# csi.net
KiCad netlist of a schematic drawn in Altium Designer
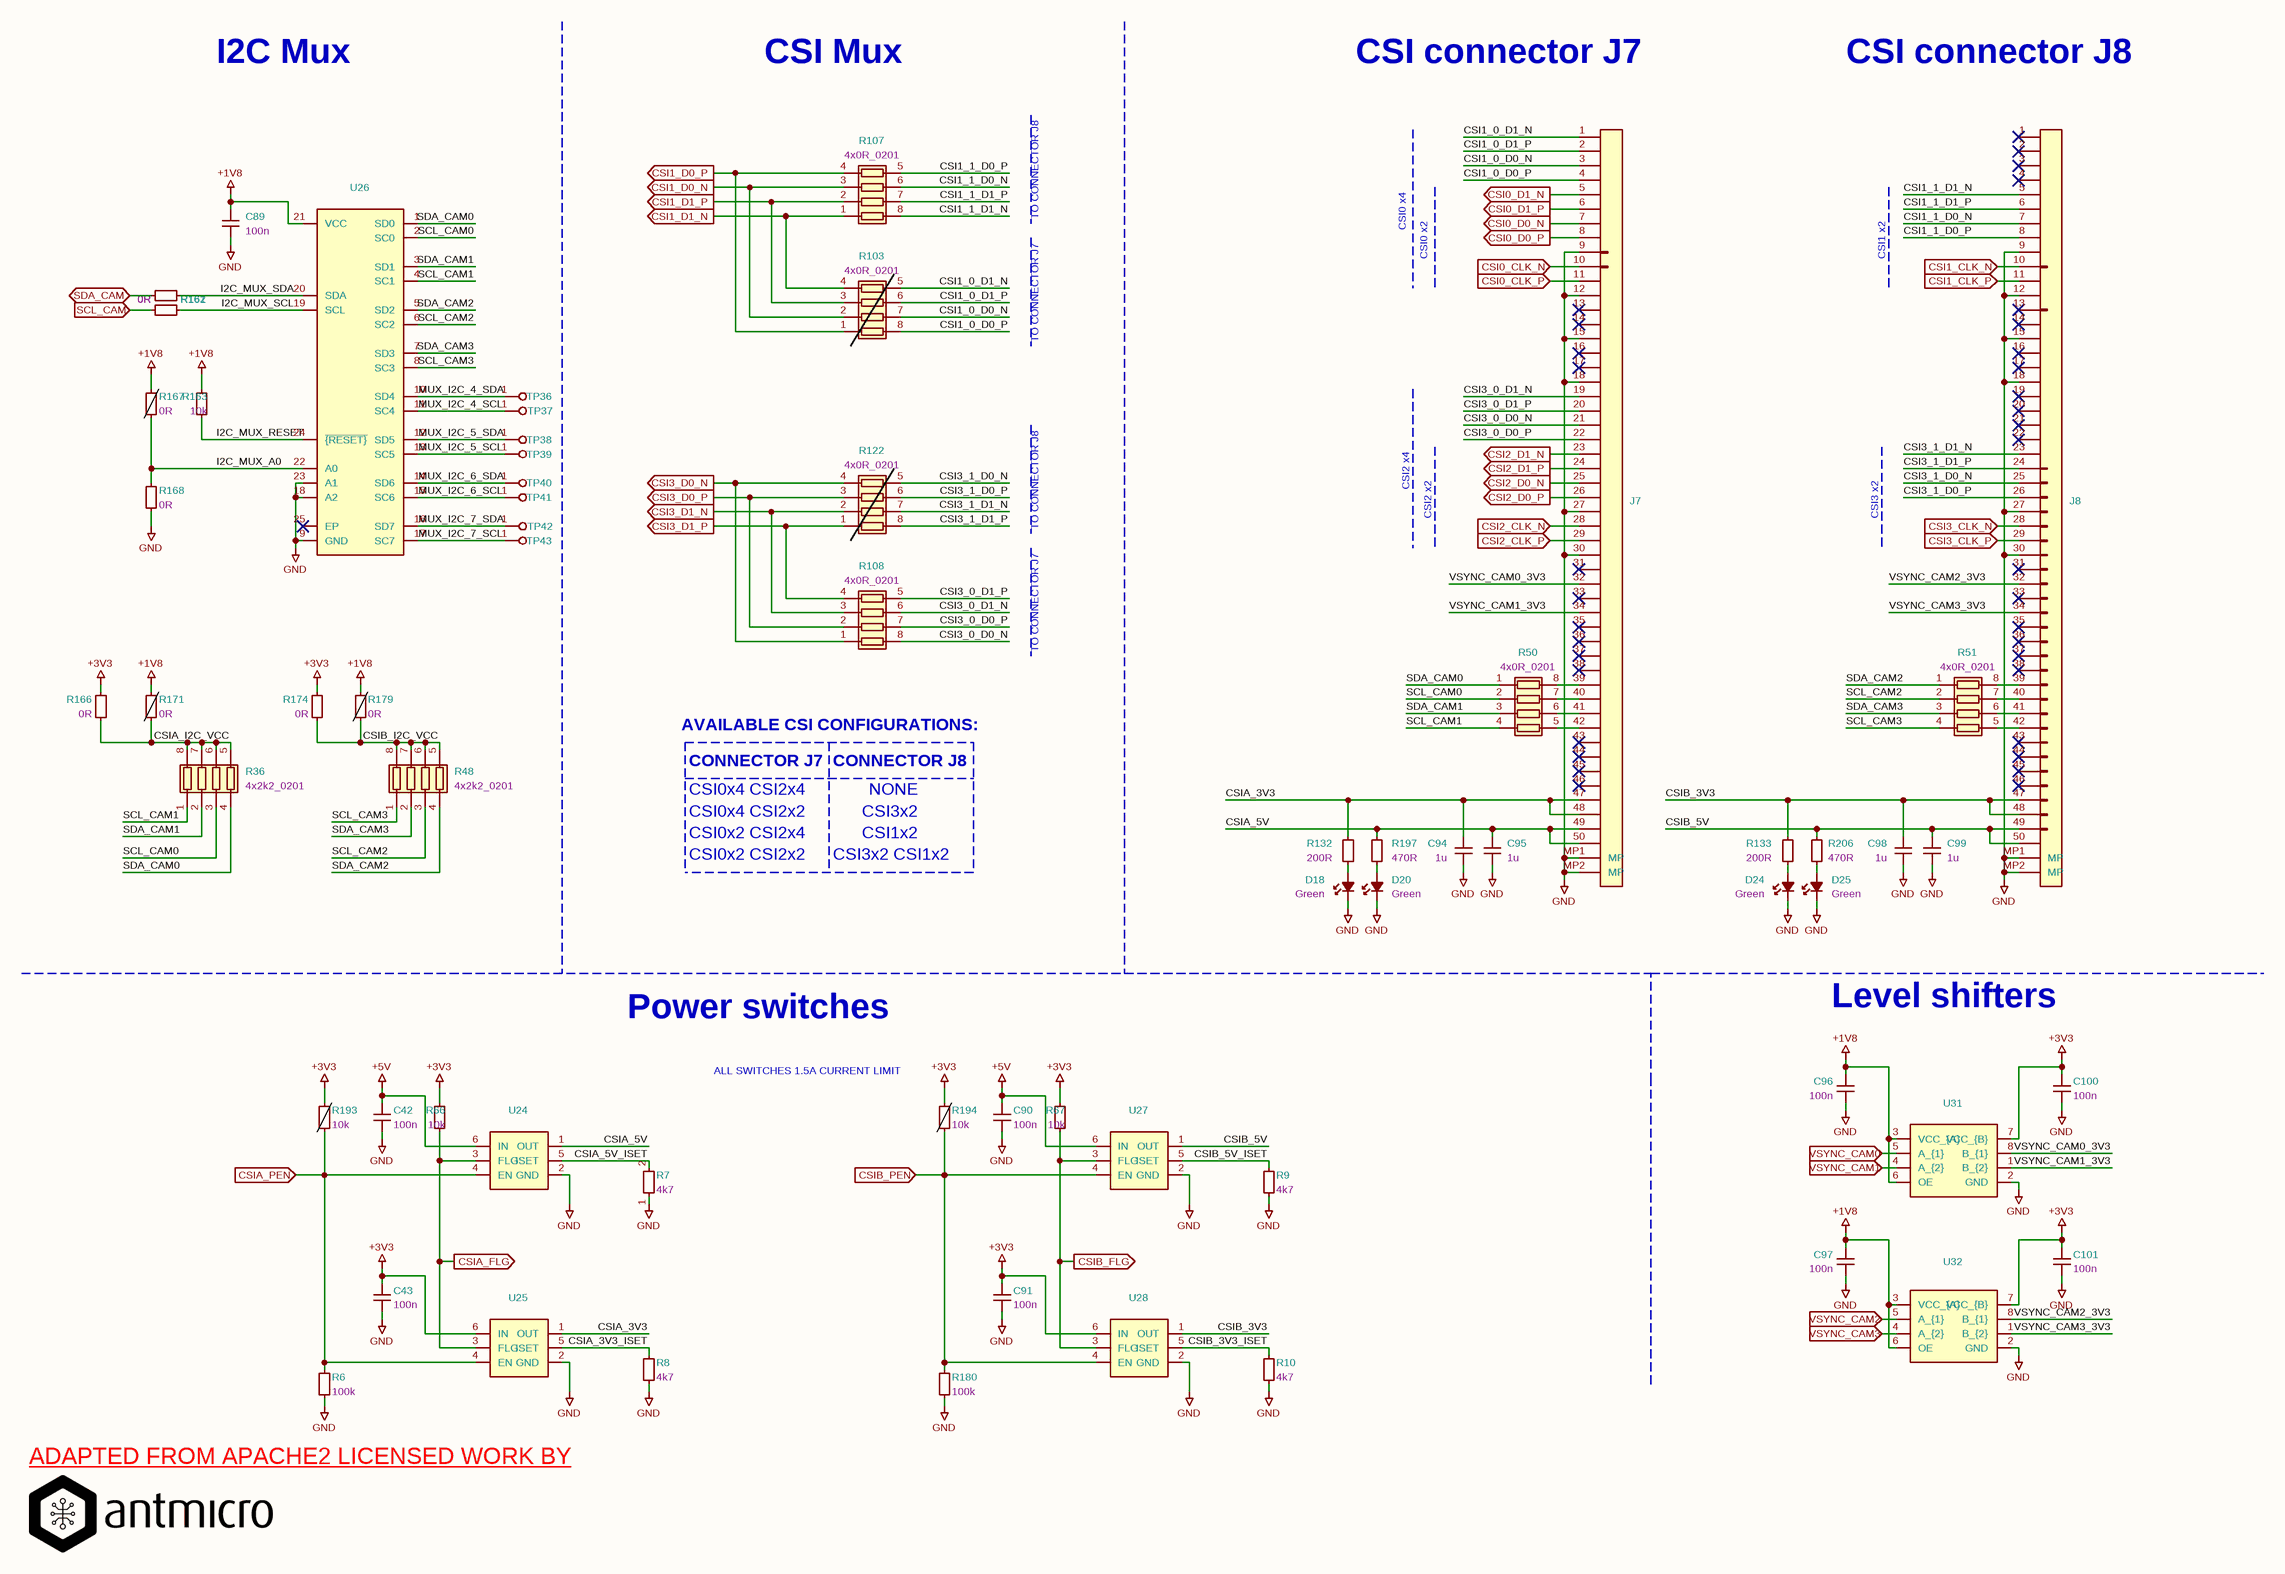
[diagram p0: csi.SchDoc]

(export (version "E")
  (design (tool "Eeschema 10.0.6"))
  (components
    (comp (ref "C42")
      (value "GRM155R61H104KE14D")
      (footprint "C_0402_1005Metric")
      (fields (field (name "VAL") "100n") (field (name "VOLTAGE") "50V") (field (name "AUTHOR") "Antmicro"))
      (libsource (lib "antmicroCapacitors0402") (part "C_100n_0402"))
    )
    (comp (ref "C43")
      (value "GRM155R61H104KE14D")
      (footprint "C_0402_1005Metric")
      (fields (field (name "VAL") "100n") (field (name "VOLTAGE") "50V") (field (name "AUTHOR") "Antmicro"))
      (libsource (lib "antmicroCapacitors0402") (part "C_100n_0402"))
    )
    (comp (ref "C89")
      (value "GRM155R61H104KE14D")
      (footprint "C_0402_1005Metric")
      (fields (field (name "VAL") "100n") (field (name "VOLTAGE") "50V") (field (name "AUTHOR") "Antmicro"))
      (libsource (lib "antmicroCapacitors0402") (part "C_100n_0402"))
    )
    (comp (ref "C90")
      (value "GRM155R61H104KE14D")
      (footprint "C_0402_1005Metric")
      (fields (field (name "VAL") "100n") (field (name "VOLTAGE") "50V") (field (name "AUTHOR") "Antmicro"))
      (libsource (lib "antmicroCapacitors0402") (part "C_100n_0402"))
    )
    (comp (ref "C91")
      (value "GRM155R61H104KE14D")
      (footprint "C_0402_1005Metric")
      (fields (field (name "VAL") "100n") (field (name "VOLTAGE") "50V") (field (name "AUTHOR") "Antmicro"))
      (libsource (lib "antmicroCapacitors0402") (part "C_100n_0402"))
    )
    (comp (ref "C94")
      (value "C1005X6S1A105K050BC")
      (footprint "C_0402_1005Metric")
      (fields (field (name "VAL") "1u") (field (name "AUTHOR") "Antmicro"))
      (libsource (lib "antmicroCapacitors0402") (part "C_1u_0402"))
    )
    (comp (ref "C95")
      (value "C1005X6S1A105K050BC")
      (footprint "C_0402_1005Metric")
      (fields (field (name "VAL") "1u") (field (name "AUTHOR") "Antmicro"))
      (libsource (lib "antmicroCapacitors0402") (part "C_1u_0402"))
    )
    (comp (ref "C96")
      (value "GRM155R61H104KE14D")
      (footprint "C_0402_1005Metric")
      (fields (field (name "VAL") "100n") (field (name "VOLTAGE") "50V") (field (name "AUTHOR") "Antmicro"))
      (libsource (lib "antmicroCapacitors0402") (part "C_100n_0402"))
    )
    (comp (ref "C97")
      (value "GRM155R61H104KE14D")
      (footprint "C_0402_1005Metric")
      (fields (field (name "VAL") "100n") (field (name "VOLTAGE") "50V") (field (name "AUTHOR") "Antmicro"))
      (libsource (lib "antmicroCapacitors0402") (part "C_100n_0402"))
    )
    (comp (ref "C98")
      (value "C1005X6S1A105K050BC")
      (footprint "C_0402_1005Metric")
      (fields (field (name "VAL") "1u") (field (name "AUTHOR") "Antmicro"))
      (libsource (lib "antmicroCapacitors0402") (part "C_1u_0402"))
    )
    (comp (ref "C99")
      (value "C1005X6S1A105K050BC")
      (footprint "C_0402_1005Metric")
      (fields (field (name "VAL") "1u") (field (name "AUTHOR") "Antmicro"))
      (libsource (lib "antmicroCapacitors0402") (part "C_1u_0402"))
    )
    (comp (ref "C100")
      (value "GRM155R61H104KE14D")
      (footprint "C_0402_1005Metric")
      (fields (field (name "VAL") "100n") (field (name "VOLTAGE") "50V") (field (name "AUTHOR") "Antmicro"))
      (libsource (lib "antmicroCapacitors0402") (part "C_100n_0402"))
    )
    (comp (ref "C101")
      (value "GRM155R61H104KE14D")
      (footprint "C_0402_1005Metric")
      (fields (field (name "VAL") "100n") (field (name "VOLTAGE") "50V") (field (name "AUTHOR") "Antmicro"))
      (libsource (lib "antmicroCapacitors0402") (part "C_100n_0402"))
    )
    (comp (ref "D18")
      (value "LTST-C190GKT")
      (footprint "LED_0603_1608Metric_G")
      (fields (field (name "COLOR") "Green") (field (name "AUTHOR") "Antmicro"))
      (libsource (lib "antmicroLEDIndicationDiscrete") (part "LED_G_0603_LTST-C190GKT"))
    )
    (comp (ref "D20")
      (value "LTST-C190GKT")
      (footprint "LED_0603_1608Metric_G")
      (fields (field (name "COLOR") "Green") (field (name "AUTHOR") "Antmicro"))
      (libsource (lib "antmicroLEDIndicationDiscrete") (part "LED_G_0603_LTST-C190GKT"))
    )
    (comp (ref "D24")
      (value "LTST-C190GKT")
      (footprint "LED_0603_1608Metric_G")
      (fields (field (name "COLOR") "Green") (field (name "AUTHOR") "Antmicro"))
      (libsource (lib "antmicroLEDIndicationDiscrete") (part "LED_G_0603_LTST-C190GKT"))
    )
    (comp (ref "D25")
      (value "LTST-C190GKT")
      (footprint "LED_0603_1608Metric_G")
      (fields (field (name "COLOR") "Green") (field (name "AUTHOR") "Antmicro"))
      (libsource (lib "antmicroLEDIndicationDiscrete") (part "LED_G_0603_LTST-C190GKT"))
    )
    (comp (ref "J7")
      (value "68715014522")
      (footprint "Conn_FFC_WE_68715014x22")
      (fields (field (name "AUTHOR") "Antmicro"))
      (libsource (lib "antmicroFCCConnectors") (part "Conn_FFC_WE_68715014522"))
    )
    (comp (ref "J8")
      (value "68715014522")
      (footprint "Conn_FFC_WE_68715014x22")
      (fields (field (name "AUTHOR") "Antmicro"))
      (libsource (lib "antmicroFCCConnectors") (part "Conn_FFC_WE_68715014522"))
    )
    (comp (ref "R6")
      (value "CR0402-FX-1003GLF")
      (footprint "R_0402_1005Metric")
      (fields (field (name "VAL") "100k") (field (name "TOLERANCE") "1%") (field (name "AUTHOR") "Antmicro"))
      (libsource (lib "antmicroResistors0402") (part "R_100k_0402"))
    )
    (comp (ref "R7")
      (value "CR0402-FX-4701GLF")
      (footprint "R_0402_1005Metric")
      (fields (field (name "VAL") "4k7") (field (name "TOLERANCE") "1%") (field (name "AUTHOR") "Antmicro"))
      (libsource (lib "antmicroResistors0402") (part "R_4k7_0402"))
    )
    (comp (ref "R8")
      (value "CR0402-FX-4701GLF")
      (footprint "R_0402_1005Metric")
      (fields (field (name "VAL") "4k7") (field (name "TOLERANCE") "1%") (field (name "AUTHOR") "Antmicro"))
      (libsource (lib "") (part "R_4k7_0402_1"))
    )
    (comp (ref "R9")
      (value "CR0402-FX-4701GLF")
      (footprint "R_0402_1005Metric")
      (fields (field (name "VAL") "4k7") (field (name "TOLERANCE") "1%") (field (name "AUTHOR") "Antmicro"))
      (libsource (lib "") (part "R_4k7_0402_1"))
    )
    (comp (ref "R10")
      (value "CR0402-FX-4701GLF")
      (footprint "R_0402_1005Metric")
      (fields (field (name "VAL") "4k7") (field (name "TOLERANCE") "1%") (field (name "AUTHOR") "Antmicro"))
      (libsource (lib "") (part "R_4k7_0402_1"))
    )
    (comp (ref "R36")
      (value "EXB-18V222JX")
      (footprint "R_Array_4x0201_Panasonic_EXB18V")
      (fields (field (name "VAL") "4x2k2_0201") (field (name "AUTHOR") "Antmicro"))
      (libsource (lib "antmicroResistorNetworksArrays") (part "R_4x2k2_0201_array"))
    )
    (comp (ref "R48")
      (value "EXB-18V222JX")
      (footprint "R_Array_4x0201_Panasonic_EXB18V")
      (fields (field (name "VAL") "4x2k2_0201") (field (name "AUTHOR") "Antmicro"))
      (libsource (lib "antmicroResistorNetworksArrays") (part "R_4x2k2_0201_array"))
    )
    (comp (ref "R50")
      (value "EXB-18VR000X")
      (footprint "R_Array_4x0201_Panasonic_EXB18V")
      (fields (field (name "VAL") "4x0R_0201") (field (name "AUTHOR") "Antmicro"))
      (libsource (lib "antmicroResistorNetworksArrays") (part "R_4x0R_0201_array"))
    )
    (comp (ref "R51")
      (value "EXB-18VR000X")
      (footprint "R_Array_4x0201_Panasonic_EXB18V")
      (fields (field (name "VAL") "4x0R_0201") (field (name "AUTHOR") "Antmicro"))
      (libsource (lib "antmicroResistorNetworksArrays") (part "R_4x0R_0201_array"))
    )
    (comp (ref "R66")
      (value "CR0402-FX-1002GLF")
      (footprint "R_0402_1005Metric")
      (fields (field (name "VAL") "10k") (field (name "TOLERANCE") "1%") (field (name "AUTHOR") "Antmicro"))
      (libsource (lib "antmicroResistors0402") (part "R_10k_0402"))
    )
    (comp (ref "R67")
      (value "CR0402-FX-1002GLF")
      (footprint "R_0402_1005Metric")
      (fields (field (name "VAL") "10k") (field (name "TOLERANCE") "1%") (field (name "AUTHOR") "Antmicro"))
      (libsource (lib "antmicroResistors0402") (part "R_10k_0402"))
    )
    (comp (ref "R103")
      (value "EXB-18VR000X")
      (footprint "R_Array_4x0201_Panasonic_EXB18V")
      (fields (field (name "VAL") "4x0R_0201") (field (name "AUTHOR") "Antmicro"))
      (libsource (lib "") (part "R_4x0R_0201_array_1"))
    )
    (comp (ref "R107")
      (value "EXB-18VR000X")
      (footprint "R_Array_4x0201_Panasonic_EXB18V")
      (fields (field (name "VAL") "4x0R_0201") (field (name "AUTHOR") "Antmicro"))
      (libsource (lib "") (part "R_4x0R_0201_array_1"))
    )
    (comp (ref "R108")
      (value "EXB-18VR000X")
      (footprint "R_Array_4x0201_Panasonic_EXB18V")
      (fields (field (name "VAL") "4x0R_0201") (field (name "AUTHOR") "Antmicro"))
      (libsource (lib "") (part "R_4x0R_0201_array_1"))
    )
    (comp (ref "R122")
      (value "EXB-18VR000X")
      (footprint "R_Array_4x0201_Panasonic_EXB18V")
      (fields (field (name "VAL") "4x0R_0201") (field (name "AUTHOR") "Antmicro"))
      (libsource (lib "") (part "R_4x0R_0201_array_1"))
    )
    (comp (ref "R132")
      (value "CR0402-FX-2000GLF")
      (footprint "R_0402_1005Metric")
      (fields (field (name "VAL") "200R") (field (name "TOLERANCE") "1%") (field (name "AUTHOR") "Antmicro"))
      (libsource (lib "jetson-orin-baseboard") (part "R_200R_0402"))
    )
    (comp (ref "R133")
      (value "CR0402-FX-2000GLF")
      (footprint "R_0402_1005Metric")
      (fields (field (name "VAL") "200R") (field (name "TOLERANCE") "1%") (field (name "AUTHOR") "Antmicro"))
      (libsource (lib "jetson-orin-baseboard") (part "R_200R_0402"))
    )
    (comp (ref "R161")
      (value "ERJ2GE0R00X")
      (footprint "R_0402_1005Metric")
      (fields (field (name "VAL") "0R") (field (name "AUTHOR") "Antmicro"))
      (libsource (lib "antmicroResistors0402") (part "R_0R_0402"))
    )
    (comp (ref "R162")
      (value "ERJ2GE0R00X")
      (footprint "R_0402_1005Metric")
      (fields (field (name "VAL") "0R") (field (name "AUTHOR") "Antmicro"))
      (libsource (lib "") (part "R_0R_0402_1"))
    )
    (comp (ref "R163")
      (value "CR0402-FX-1002GLF")
      (footprint "R_0402_1005Metric")
      (fields (field (name "VAL") "10k") (field (name "TOLERANCE") "1%") (field (name "AUTHOR") "Antmicro"))
      (libsource (lib "antmicroResistors0402") (part "R_10k_0402"))
    )
    (comp (ref "R166")
      (value "ERJ2GE0R00X")
      (footprint "R_0402_1005Metric")
      (fields (field (name "VAL") "0R") (field (name "AUTHOR") "Antmicro"))
      (libsource (lib "") (part "R_0R_0402_2"))
    )
    (comp (ref "R167")
      (value "ERJ2GE0R00X")
      (footprint "R_0402_1005Metric")
      (fields (field (name "VAL") "0R") (field (name "AUTHOR") "Antmicro"))
      (libsource (lib "") (part "R_0R_0402_2"))
    )
    (comp (ref "R168")
      (value "ERJ2GE0R00X")
      (footprint "R_0402_1005Metric")
      (fields (field (name "VAL") "0R") (field (name "AUTHOR") "Antmicro"))
      (libsource (lib "") (part "R_0R_0402_2"))
    )
    (comp (ref "R171")
      (value "ERJ2GE0R00X")
      (footprint "R_0402_1005Metric")
      (fields (field (name "VAL") "0R") (field (name "AUTHOR") "Antmicro"))
      (libsource (lib "") (part "R_0R_0402_2"))
    )
    (comp (ref "R174")
      (value "ERJ2GE0R00X")
      (footprint "R_0402_1005Metric")
      (fields (field (name "VAL") "0R") (field (name "AUTHOR") "Antmicro"))
      (libsource (lib "") (part "R_0R_0402_2"))
    )
    (comp (ref "R179")
      (value "ERJ2GE0R00X")
      (footprint "R_0402_1005Metric")
      (fields (field (name "VAL") "0R") (field (name "AUTHOR") "Antmicro"))
      (libsource (lib "") (part "R_0R_0402_2"))
    )
    (comp (ref "R180")
      (value "CR0402-FX-1003GLF")
      (footprint "R_0402_1005Metric")
      (fields (field (name "VAL") "100k") (field (name "TOLERANCE") "1%") (field (name "AUTHOR") "Antmicro"))
      (libsource (lib "antmicroResistors0402") (part "R_100k_0402"))
    )
    (comp (ref "R193")
      (value "CR0402-FX-1002GLF")
      (footprint "R_0402_1005Metric")
      (fields (field (name "VAL") "10k") (field (name "TOLERANCE") "1%") (field (name "AUTHOR") "Antmicro"))
      (libsource (lib "") (part "R_10k_0402_1"))
    )
    (comp (ref "R194")
      (value "CR0402-FX-1002GLF")
      (footprint "R_0402_1005Metric")
      (fields (field (name "VAL") "10k") (field (name "TOLERANCE") "1%") (field (name "AUTHOR") "Antmicro"))
      (libsource (lib "") (part "R_10k_0402_1"))
    )
    (comp (ref "R197")
      (value "CR0402-FX-4700GLF")
      (footprint "R_0402_1005Metric")
      (fields (field (name "VAL") "470R") (field (name "TOLERANCE") "1%") (field (name "AUTHOR") "Antmicro"))
      (libsource (lib "antmicroResistors0402") (part "R_470R_0402"))
    )
    (comp (ref "R206")
      (value "CR0402-FX-4700GLF")
      (footprint "R_0402_1005Metric")
      (fields (field (name "VAL") "470R") (field (name "TOLERANCE") "1%") (field (name "AUTHOR") "Antmicro"))
      (libsource (lib "antmicroResistors0402") (part "R_470R_0402"))
    )
    (comp (ref "TP36")
      (value "TP_0.75mm_SMD")
      (footprint "TP_SMD_0.75mm")
      (fields (field (name "AUTHOR") "Antmicro"))
      (libsource (lib "antmicroTestPoints") (part "TP_0.75mm_SMD"))
    )
    (comp (ref "TP37")
      (value "TP_0.75mm_SMD")
      (footprint "TP_SMD_0.75mm")
      (fields (field (name "AUTHOR") "Antmicro"))
      (libsource (lib "antmicroTestPoints") (part "TP_0.75mm_SMD"))
    )
    (comp (ref "TP38")
      (value "TP_0.75mm_SMD")
      (footprint "TP_SMD_0.75mm")
      (fields (field (name "AUTHOR") "Antmicro"))
      (libsource (lib "antmicroTestPoints") (part "TP_0.75mm_SMD"))
    )
    (comp (ref "TP39")
      (value "TP_0.75mm_SMD")
      (footprint "TP_SMD_0.75mm")
      (fields (field (name "AUTHOR") "Antmicro"))
      (libsource (lib "antmicroTestPoints") (part "TP_0.75mm_SMD"))
    )
    (comp (ref "TP40")
      (value "TP_0.75mm_SMD")
      (footprint "TP_SMD_0.75mm")
      (fields (field (name "AUTHOR") "Antmicro"))
      (libsource (lib "antmicroTestPoints") (part "TP_0.75mm_SMD"))
    )
    (comp (ref "TP41")
      (value "TP_0.75mm_SMD")
      (footprint "TP_SMD_0.75mm")
      (fields (field (name "AUTHOR") "Antmicro"))
      (libsource (lib "antmicroTestPoints") (part "TP_0.75mm_SMD"))
    )
    (comp (ref "TP42")
      (value "TP_0.75mm_SMD")
      (footprint "TP_SMD_0.75mm")
      (fields (field (name "AUTHOR") "Antmicro"))
      (libsource (lib "antmicroTestPoints") (part "TP_0.75mm_SMD"))
    )
    (comp (ref "TP43")
      (value "TP_0.75mm_SMD")
      (footprint "TP_SMD_0.75mm")
      (fields (field (name "AUTHOR") "Antmicro"))
      (libsource (lib "antmicroTestPoints") (part "TP_0.75mm_SMD"))
    )
    (comp (ref "U24")
      (value "AP22615AWU-7")
      (footprint "TSOT23-6")
      (fields (field (name "AUTHOR") "Antmicro"))
      (libsource (lib "antmicroPMICPowerDistributionSwitchesLoadDrivers") (part "AP22615A_TSOT26"))
    )
    (comp (ref "U25")
      (value "AP22615AWU-7")
      (footprint "TSOT23-6")
      (fields (field (name "AUTHOR") "Antmicro"))
      (libsource (lib "antmicroPMICPowerDistributionSwitchesLoadDrivers") (part "AP22615A_TSOT26"))
    )
    (comp (ref "U26")
      (value "PI4MSD5V9548AZDEX")
      (footprint "VQFN-24-1EP_3.8x3.8x1.0mm_P0.5mm")
      (fields (field (name "AUTHOR") "Antmicro"))
      (libsource (lib "antmicroLogicSignalSwitchesMultiplexersDecoders") (part "PI4MSD5V9548AZDEX"))
    )
    (comp (ref "U27")
      (value "AP22615AWU-7")
      (footprint "TSOT23-6")
      (fields (field (name "AUTHOR") "Antmicro"))
      (libsource (lib "antmicroPMICPowerDistributionSwitchesLoadDrivers") (part "AP22615A_TSOT26"))
    )
    (comp (ref "U28")
      (value "AP22615AWU-7")
      (footprint "TSOT23-6")
      (fields (field (name "AUTHOR") "Antmicro"))
      (libsource (lib "antmicroPMICPowerDistributionSwitchesLoadDrivers") (part "AP22615A_TSOT26"))
    )
    (comp (ref "U31")
      (value "NTS0102GT")
      (footprint "XSON-8_1x1.95mm_P0.5mm")
      (fields (field (name "AUTHOR") "Antmicro"))
      (libsource (lib "antmicroLogicTranslatorsLevelShifters") (part "NTS0102_XSON"))
    )
    (comp (ref "U32")
      (value "NTS0102GT")
      (footprint "XSON-8_1x1.95mm_P0.5mm")
      (fields (field (name "AUTHOR") "Antmicro"))
      (libsource (lib "antmicroLogicTranslatorsLevelShifters") (part "NTS0102_XSON"))
    )
  )
  (nets
    (net (code "1") (name "+1V8") (class "Default")
      (node (ref "C89") (pin "2") (pinfunction "2_2") (pintype "passive"))
      (node (ref "C96") (pin "2") (pinfunction "2_2") (pintype "passive"))
      (node (ref "C97") (pin "2") (pinfunction "2_2") (pintype "passive"))
      (node (ref "R163") (pin "1") (pinfunction "1_1") (pintype "passive"))
      (node (ref "R167") (pin "2") (pinfunction "2_2") (pintype "passive"))
      (node (ref "R171") (pin "2") (pinfunction "2_2") (pintype "passive"))
      (node (ref "R179") (pin "2") (pinfunction "2_2") (pintype "passive"))
      (node (ref "U26") (pin "21") (pinfunction "VCC_21") (pintype "passive"))
      (node (ref "U31") (pin "3") (pinfunction "VCC_{A}_3") (pintype "passive"))
      (node (ref "U31") (pin "6") (pinfunction "OE_6") (pintype "passive"))
      (node (ref "U32") (pin "3") (pinfunction "VCC_{A}_3") (pintype "passive"))
      (node (ref "U32") (pin "6") (pinfunction "OE_6") (pintype "passive"))
    )
    (net (code "2") (name "+3V3") (class "Default")
      (node (ref "C100") (pin "2") (pinfunction "2_2") (pintype "passive"))
      (node (ref "C101") (pin "2") (pinfunction "2_2") (pintype "passive"))
      (node (ref "C43") (pin "1") (pinfunction "1_1") (pintype "passive"))
      (node (ref "C91") (pin "1") (pinfunction "1_1") (pintype "passive"))
      (node (ref "R166") (pin "2") (pinfunction "2_2") (pintype "passive"))
      (node (ref "R174") (pin "2") (pinfunction "2_2") (pintype "passive"))
      (node (ref "R193") (pin "2") (pinfunction "2_2") (pintype "passive"))
      (node (ref "R194") (pin "2") (pinfunction "2_2") (pintype "passive"))
      (node (ref "R66") (pin "1") (pinfunction "1_1") (pintype "passive"))
      (node (ref "R67") (pin "1") (pinfunction "1_1") (pintype "passive"))
      (node (ref "U25") (pin "6") (pinfunction "IN_6") (pintype "passive"))
      (node (ref "U28") (pin "6") (pinfunction "IN_6") (pintype "passive"))
      (node (ref "U31") (pin "7") (pinfunction "VCC_{B}_7") (pintype "passive"))
      (node (ref "U32") (pin "7") (pinfunction "VCC_{B}_7") (pintype "passive"))
    )
    (net (code "3") (name "+5V") (class "Default")
      (node (ref "C42") (pin "1") (pinfunction "1_1") (pintype "passive"))
      (node (ref "C90") (pin "1") (pinfunction "1_1") (pintype "passive"))
      (node (ref "U24") (pin "6") (pinfunction "IN_6") (pintype "passive"))
      (node (ref "U27") (pin "6") (pinfunction "IN_6") (pintype "passive"))
    )
    (net (code "4") (name "/CSI0_CLK_N") (class "Default")
      (node (ref "J7") (pin "10") (pinfunction "10_10") (pintype "passive"))
    )
    (net (code "5") (name "/CSI0_CLK_P") (class "Default")
      (node (ref "J7") (pin "11") (pinfunction "11_11") (pintype "passive"))
    )
    (net (code "6") (name "/CSI0_D0_N") (class "Default")
      (node (ref "J7") (pin "7") (pinfunction "7_7") (pintype "passive"))
    )
    (net (code "7") (name "/CSI0_D0_P") (class "Default")
      (node (ref "J7") (pin "8") (pinfunction "8_8") (pintype "passive"))
    )
    (net (code "8") (name "/CSI0_D1_N") (class "Default")
      (node (ref "J7") (pin "5") (pinfunction "5_5") (pintype "passive"))
    )
    (net (code "9") (name "/CSI0_D1_P") (class "Default")
      (node (ref "J7") (pin "6") (pinfunction "6_6") (pintype "passive"))
    )
    (net (code "10") (name "/CSI1_0_D0_N") (class "Default")
      (node (ref "J7") (pin "3") (pinfunction "3_3") (pintype "passive"))
      (node (ref "R103") (pin "7") (pinfunction "R2.2_7") (pintype "passive"))
    )
    (net (code "11") (name "/CSI1_0_D0_P") (class "Default")
      (node (ref "J7") (pin "4") (pinfunction "4_4") (pintype "passive"))
      (node (ref "R103") (pin "8") (pinfunction "R1.2_8") (pintype "passive"))
    )
    (net (code "12") (name "/CSI1_0_D1_N") (class "Default")
      (node (ref "J7") (pin "1") (pinfunction "1_1") (pintype "passive"))
      (node (ref "R103") (pin "5") (pinfunction "R4.2_5") (pintype "passive"))
    )
    (net (code "13") (name "/CSI1_0_D1_P") (class "Default")
      (node (ref "J7") (pin "2") (pinfunction "2_2") (pintype "passive"))
      (node (ref "R103") (pin "6") (pinfunction "R3.2_6") (pintype "passive"))
    )
    (net (code "14") (name "/CSI1_1_D0_N") (class "Default")
      (node (ref "J8") (pin "7") (pinfunction "7_7") (pintype "passive"))
      (node (ref "R107") (pin "6") (pinfunction "R3.2_6") (pintype "passive"))
    )
    (net (code "15") (name "/CSI1_1_D0_P") (class "Default")
      (node (ref "J8") (pin "8") (pinfunction "8_8") (pintype "passive"))
      (node (ref "R107") (pin "5") (pinfunction "R4.2_5") (pintype "passive"))
    )
    (net (code "16") (name "/CSI1_1_D1_N") (class "Default")
      (node (ref "J8") (pin "5") (pinfunction "5_5") (pintype "passive"))
      (node (ref "R107") (pin "8") (pinfunction "R1.2_8") (pintype "passive"))
    )
    (net (code "17") (name "/CSI1_1_D1_P") (class "Default")
      (node (ref "J8") (pin "6") (pinfunction "6_6") (pintype "passive"))
      (node (ref "R107") (pin "7") (pinfunction "R2.2_7") (pintype "passive"))
    )
    (net (code "18") (name "/CSI1_CLK_N") (class "Default")
      (node (ref "J8") (pin "10") (pinfunction "10_10") (pintype "passive"))
    )
    (net (code "19") (name "/CSI1_CLK_P") (class "Default")
      (node (ref "J8") (pin "11") (pinfunction "11_11") (pintype "passive"))
    )
    (net (code "20") (name "/CSI1_D0_N") (class "Default")
      (node (ref "R103") (pin "2") (pinfunction "R2.1_2") (pintype "passive"))
      (node (ref "R107") (pin "3") (pinfunction "R3.1_3") (pintype "passive"))
    )
    (net (code "21") (name "/CSI1_D0_P") (class "Default")
      (node (ref "R103") (pin "1") (pinfunction "R1.1_1") (pintype "passive"))
      (node (ref "R107") (pin "4") (pinfunction "R4.1_4") (pintype "passive"))
    )
    (net (code "22") (name "/CSI1_D1_N") (class "Default")
      (node (ref "R103") (pin "4") (pinfunction "R4.1_4") (pintype "passive"))
      (node (ref "R107") (pin "1") (pinfunction "R1.1_1") (pintype "passive"))
    )
    (net (code "23") (name "/CSI1_D1_P") (class "Default")
      (node (ref "R103") (pin "3") (pinfunction "R3.1_3") (pintype "passive"))
      (node (ref "R107") (pin "2") (pinfunction "R2.1_2") (pintype "passive"))
    )
    (net (code "24") (name "/CSI2_CLK_N") (class "Default")
      (node (ref "J7") (pin "28") (pinfunction "28_28") (pintype "passive"))
    )
    (net (code "25") (name "/CSI2_CLK_P") (class "Default")
      (node (ref "J7") (pin "29") (pinfunction "29_29") (pintype "passive"))
    )
    (net (code "26") (name "/CSI2_D0_N") (class "Default")
      (node (ref "J7") (pin "25") (pinfunction "25_25") (pintype "passive"))
    )
    (net (code "27") (name "/CSI2_D0_P") (class "Default")
      (node (ref "J7") (pin "26") (pinfunction "26_26") (pintype "passive"))
    )
    (net (code "28") (name "/CSI2_D1_N") (class "Default")
      (node (ref "J7") (pin "23") (pinfunction "23_23") (pintype "passive"))
    )
    (net (code "29") (name "/CSI2_D1_P") (class "Default")
      (node (ref "J7") (pin "24") (pinfunction "24_24") (pintype "passive"))
    )
    (net (code "30") (name "/CSI3_0_D0_N") (class "Default")
      (node (ref "J7") (pin "21") (pinfunction "21_21") (pintype "passive"))
      (node (ref "R108") (pin "8") (pinfunction "R1.2_8") (pintype "passive"))
    )
    (net (code "31") (name "/CSI3_0_D0_P") (class "Default")
      (node (ref "J7") (pin "22") (pinfunction "22_22") (pintype "passive"))
      (node (ref "R108") (pin "7") (pinfunction "R2.2_7") (pintype "passive"))
    )
    (net (code "32") (name "/CSI3_0_D1_N") (class "Default")
      (node (ref "J7") (pin "19") (pinfunction "19_19") (pintype "passive"))
      (node (ref "R108") (pin "6") (pinfunction "R3.2_6") (pintype "passive"))
    )
    (net (code "33") (name "/CSI3_0_D1_P") (class "Default")
      (node (ref "J7") (pin "20") (pinfunction "20_20") (pintype "passive"))
      (node (ref "R108") (pin "5") (pinfunction "R4.2_5") (pintype "passive"))
    )
    (net (code "34") (name "/CSI3_1_D0_N") (class "Default")
      (node (ref "J8") (pin "25") (pinfunction "25_25") (pintype "passive"))
      (node (ref "R122") (pin "5") (pinfunction "R4.2_5") (pintype "passive"))
    )
    (net (code "35") (name "/CSI3_1_D0_P") (class "Default")
      (node (ref "J8") (pin "26") (pinfunction "26_26") (pintype "passive"))
      (node (ref "R122") (pin "6") (pinfunction "R3.2_6") (pintype "passive"))
    )
    (net (code "36") (name "/CSI3_1_D1_N") (class "Default")
      (node (ref "J8") (pin "23") (pinfunction "23_23") (pintype "passive"))
      (node (ref "R122") (pin "7") (pinfunction "R2.2_7") (pintype "passive"))
    )
    (net (code "37") (name "/CSI3_1_D1_P") (class "Default")
      (node (ref "J8") (pin "24") (pinfunction "24_24") (pintype "passive"))
      (node (ref "R122") (pin "8") (pinfunction "R1.2_8") (pintype "passive"))
    )
    (net (code "38") (name "/CSI3_CLK_N") (class "Default")
      (node (ref "J8") (pin "28") (pinfunction "28_28") (pintype "passive"))
    )
    (net (code "39") (name "/CSI3_CLK_P") (class "Default")
      (node (ref "J8") (pin "29") (pinfunction "29_29") (pintype "passive"))
    )
    (net (code "40") (name "/CSI3_D0_N") (class "Default")
      (node (ref "R108") (pin "1") (pinfunction "R1.1_1") (pintype "passive"))
      (node (ref "R122") (pin "4") (pinfunction "R4.1_4") (pintype "passive"))
    )
    (net (code "41") (name "/CSI3_D0_P") (class "Default")
      (node (ref "R108") (pin "2") (pinfunction "R2.1_2") (pintype "passive"))
      (node (ref "R122") (pin "3") (pinfunction "R3.1_3") (pintype "passive"))
    )
    (net (code "42") (name "/CSI3_D1_N") (class "Default")
      (node (ref "R108") (pin "3") (pinfunction "R3.1_3") (pintype "passive"))
      (node (ref "R122") (pin "2") (pinfunction "R2.1_2") (pintype "passive"))
    )
    (net (code "43") (name "/CSI3_D1_P") (class "Default")
      (node (ref "R108") (pin "4") (pinfunction "R4.1_4") (pintype "passive"))
      (node (ref "R122") (pin "1") (pinfunction "R1.1_1") (pintype "passive"))
    )
    (net (code "44") (name "/CSIA_3V3") (class "Default")
      (node (ref "C94") (pin "2") (pinfunction "2_2") (pintype "passive"))
      (node (ref "J7") (pin "47") (pinfunction "47_47") (pintype "passive"))
      (node (ref "J7") (pin "48") (pinfunction "48_48") (pintype "passive"))
      (node (ref "R132") (pin "2") (pinfunction "2_2") (pintype "passive"))
      (node (ref "U25") (pin "1") (pinfunction "OUT_1") (pintype "passive"))
    )
    (net (code "45") (name "/CSIA_3V3_ISET") (class "Default")
      (node (ref "R8") (pin "2") (pinfunction "2_2") (pintype "passive"))
      (node (ref "U25") (pin "5") (pinfunction "ISET_5") (pintype "passive"))
    )
    (net (code "46") (name "/CSIA_5V") (class "Default")
      (node (ref "C95") (pin "2") (pinfunction "2_2") (pintype "passive"))
      (node (ref "J7") (pin "49") (pinfunction "49_49") (pintype "passive"))
      (node (ref "J7") (pin "50") (pinfunction "50_50") (pintype "passive"))
      (node (ref "R197") (pin "2") (pinfunction "2_2") (pintype "passive"))
      (node (ref "U24") (pin "1") (pinfunction "OUT_1") (pintype "passive"))
    )
    (net (code "47") (name "/CSIA_5V_ISET") (class "Default")
      (node (ref "R7") (pin "2") (pinfunction "2_2") (pintype "passive"))
      (node (ref "U24") (pin "5") (pinfunction "ISET_5") (pintype "passive"))
    )
    (net (code "48") (name "/CSIA_FLG") (class "Default")
      (node (ref "R66") (pin "2") (pinfunction "2_2") (pintype "passive"))
      (node (ref "U24") (pin "3") (pinfunction "FLG_3") (pintype "passive"))
      (node (ref "U25") (pin "3") (pinfunction "FLG_3") (pintype "passive"))
    )
    (net (code "49") (name "/CSIA_I2C_VCC") (class "Default")
      (node (ref "R166") (pin "1") (pinfunction "1_1") (pintype "passive"))
      (node (ref "R171") (pin "1") (pinfunction "1_1") (pintype "passive"))
      (node (ref "R36") (pin "5") (pinfunction "R4.2_5") (pintype "passive"))
      (node (ref "R36") (pin "6") (pinfunction "R3.2_6") (pintype "passive"))
      (node (ref "R36") (pin "7") (pinfunction "R2.2_7") (pintype "passive"))
      (node (ref "R36") (pin "8") (pinfunction "R1.2_8") (pintype "passive"))
    )
    (net (code "50") (name "/CSIA_PEN") (class "Default")
      (node (ref "R193") (pin "1") (pinfunction "1_1") (pintype "passive"))
      (node (ref "R6") (pin "2") (pinfunction "2_2") (pintype "passive"))
      (node (ref "U24") (pin "4") (pinfunction "EN_4") (pintype "passive"))
      (node (ref "U25") (pin "4") (pinfunction "EN_4") (pintype "passive"))
    )
    (net (code "51") (name "/CSIB_3V3") (class "Default")
      (node (ref "C98") (pin "2") (pinfunction "2_2") (pintype "passive"))
      (node (ref "J8") (pin "47") (pinfunction "47_47") (pintype "passive"))
      (node (ref "J8") (pin "48") (pinfunction "48_48") (pintype "passive"))
      (node (ref "R133") (pin "2") (pinfunction "2_2") (pintype "passive"))
      (node (ref "U28") (pin "1") (pinfunction "OUT_1") (pintype "passive"))
    )
    (net (code "52") (name "/CSIB_3V3_ISET") (class "Default")
      (node (ref "R10") (pin "2") (pinfunction "2_2") (pintype "passive"))
      (node (ref "U28") (pin "5") (pinfunction "ISET_5") (pintype "passive"))
    )
    (net (code "53") (name "/CSIB_5V") (class "Default")
      (node (ref "C99") (pin "2") (pinfunction "2_2") (pintype "passive"))
      (node (ref "J8") (pin "49") (pinfunction "49_49") (pintype "passive"))
      (node (ref "J8") (pin "50") (pinfunction "50_50") (pintype "passive"))
      (node (ref "R206") (pin "2") (pinfunction "2_2") (pintype "passive"))
      (node (ref "U27") (pin "1") (pinfunction "OUT_1") (pintype "passive"))
    )
    (net (code "54") (name "/CSIB_5V_ISET") (class "Default")
      (node (ref "R9") (pin "2") (pinfunction "2_2") (pintype "passive"))
      (node (ref "U27") (pin "5") (pinfunction "ISET_5") (pintype "passive"))
    )
    (net (code "55") (name "/CSIB_FLG") (class "Default")
      (node (ref "R67") (pin "2") (pinfunction "2_2") (pintype "passive"))
      (node (ref "U27") (pin "3") (pinfunction "FLG_3") (pintype "passive"))
      (node (ref "U28") (pin "3") (pinfunction "FLG_3") (pintype "passive"))
    )
    (net (code "56") (name "/CSIB_I2C_VCC") (class "Default")
      (node (ref "R174") (pin "1") (pinfunction "1_1") (pintype "passive"))
      (node (ref "R179") (pin "1") (pinfunction "1_1") (pintype "passive"))
      (node (ref "R48") (pin "5") (pinfunction "R4.2_5") (pintype "passive"))
      (node (ref "R48") (pin "6") (pinfunction "R3.2_6") (pintype "passive"))
      (node (ref "R48") (pin "7") (pinfunction "R2.2_7") (pintype "passive"))
      (node (ref "R48") (pin "8") (pinfunction "R1.2_8") (pintype "passive"))
    )
    (net (code "57") (name "/CSIB_PEN") (class "Default")
      (node (ref "R180") (pin "2") (pinfunction "2_2") (pintype "passive"))
      (node (ref "R194") (pin "1") (pinfunction "1_1") (pintype "passive"))
      (node (ref "U27") (pin "4") (pinfunction "EN_4") (pintype "passive"))
      (node (ref "U28") (pin "4") (pinfunction "EN_4") (pintype "passive"))
    )
    (net (code "58") (name "/I2C_MUX_A0") (class "Default")
      (node (ref "R167") (pin "1") (pinfunction "1_1") (pintype "passive"))
      (node (ref "R168") (pin "2") (pinfunction "2_2") (pintype "passive"))
      (node (ref "U26") (pin "22") (pinfunction "A0_22") (pintype "passive"))
    )
    (net (code "59") (name "/I2C_MUX_RESET") (class "Default")
      (node (ref "R163") (pin "2") (pinfunction "2_2") (pintype "passive"))
      (node (ref "U26") (pin "24") (pinfunction "~{{RESET}}_24") (pintype "passive"))
    )
    (net (code "60") (name "/I2C_MUX_SCL") (class "Default")
      (node (ref "R162") (pin "1") (pinfunction "1_1") (pintype "passive"))
      (node (ref "U26") (pin "19") (pinfunction "SCL_19") (pintype "passive"))
    )
    (net (code "61") (name "/I2C_MUX_SDA") (class "Default")
      (node (ref "R161") (pin "1") (pinfunction "1_1") (pintype "passive"))
      (node (ref "U26") (pin "20") (pinfunction "SDA_20") (pintype "passive"))
    )
    (net (code "62") (name "/MUX_I2C_4_SCL") (class "Default")
      (node (ref "TP37") (pin "1") (pinfunction "1_1") (pintype "passive"))
      (node (ref "U26") (pin "11") (pinfunction "SC4_11") (pintype "passive"))
    )
    (net (code "63") (name "/MUX_I2C_4_SDA") (class "Default")
      (node (ref "TP36") (pin "1") (pinfunction "1_1") (pintype "passive"))
      (node (ref "U26") (pin "10") (pinfunction "SD4_10") (pintype "passive"))
    )
    (net (code "64") (name "/MUX_I2C_5_SCL") (class "Default")
      (node (ref "TP39") (pin "1") (pinfunction "1_1") (pintype "passive"))
      (node (ref "U26") (pin "13") (pinfunction "SC5_13") (pintype "passive"))
    )
    (net (code "65") (name "/MUX_I2C_5_SDA") (class "Default")
      (node (ref "TP38") (pin "1") (pinfunction "1_1") (pintype "passive"))
      (node (ref "U26") (pin "12") (pinfunction "SD5_12") (pintype "passive"))
    )
    (net (code "66") (name "/MUX_I2C_6_SCL") (class "Default")
      (node (ref "TP41") (pin "1") (pinfunction "1_1") (pintype "passive"))
      (node (ref "U26") (pin "15") (pinfunction "SC6_15") (pintype "passive"))
    )
    (net (code "67") (name "/MUX_I2C_6_SDA") (class "Default")
      (node (ref "TP40") (pin "1") (pinfunction "1_1") (pintype "passive"))
      (node (ref "U26") (pin "14") (pinfunction "SD6_14") (pintype "passive"))
    )
    (net (code "68") (name "/MUX_I2C_7_SCL") (class "Default")
      (node (ref "TP43") (pin "1") (pinfunction "1_1") (pintype "passive"))
      (node (ref "U26") (pin "17") (pinfunction "SC7_17") (pintype "passive"))
    )
    (net (code "69") (name "/MUX_I2C_7_SDA") (class "Default")
      (node (ref "TP42") (pin "1") (pinfunction "1_1") (pintype "passive"))
      (node (ref "U26") (pin "16") (pinfunction "SD7_16") (pintype "passive"))
    )
    (net (code "70") (name "/SCL_CAM") (class "Default")
      (node (ref "R162") (pin "2") (pinfunction "2_2") (pintype "passive"))
    )
    (net (code "71") (name "/SCL_CAM0") (class "Default")
      (node (ref "R36") (pin "3") (pinfunction "R3.1_3") (pintype "passive"))
      (node (ref "R50") (pin "2") (pinfunction "R2.1_2") (pintype "passive"))
      (node (ref "U26") (pin "2") (pinfunction "SC0_2") (pintype "passive"))
    )
    (net (code "72") (name "/SCL_CAM1") (class "Default")
      (node (ref "R36") (pin "1") (pinfunction "R1.1_1") (pintype "passive"))
      (node (ref "R50") (pin "4") (pinfunction "R4.1_4") (pintype "passive"))
      (node (ref "U26") (pin "4") (pinfunction "SC1_4") (pintype "passive"))
    )
    (net (code "73") (name "/SCL_CAM2") (class "Default")
      (node (ref "R48") (pin "3") (pinfunction "R3.1_3") (pintype "passive"))
      (node (ref "R51") (pin "2") (pinfunction "R2.1_2") (pintype "passive"))
      (node (ref "U26") (pin "6") (pinfunction "SC2_6") (pintype "passive"))
    )
    (net (code "74") (name "/SCL_CAM3") (class "Default")
      (node (ref "R48") (pin "1") (pinfunction "R1.1_1") (pintype "passive"))
      (node (ref "R51") (pin "4") (pinfunction "R4.1_4") (pintype "passive"))
      (node (ref "U26") (pin "8") (pinfunction "SC3_8") (pintype "passive"))
    )
    (net (code "75") (name "/SDA_CAM") (class "Default")
      (node (ref "R161") (pin "2") (pinfunction "2_2") (pintype "passive"))
    )
    (net (code "76") (name "/SDA_CAM0") (class "Default")
      (node (ref "R36") (pin "4") (pinfunction "R4.1_4") (pintype "passive"))
      (node (ref "R50") (pin "1") (pinfunction "R1.1_1") (pintype "passive"))
      (node (ref "U26") (pin "1") (pinfunction "SD0_1") (pintype "passive"))
    )
    (net (code "77") (name "/SDA_CAM1") (class "Default")
      (node (ref "R36") (pin "2") (pinfunction "R2.1_2") (pintype "passive"))
      (node (ref "R50") (pin "3") (pinfunction "R3.1_3") (pintype "passive"))
      (node (ref "U26") (pin "3") (pinfunction "SD1_3") (pintype "passive"))
    )
    (net (code "78") (name "/SDA_CAM2") (class "Default")
      (node (ref "R48") (pin "4") (pinfunction "R4.1_4") (pintype "passive"))
      (node (ref "R51") (pin "1") (pinfunction "R1.1_1") (pintype "passive"))
      (node (ref "U26") (pin "5") (pinfunction "SD2_5") (pintype "passive"))
    )
    (net (code "79") (name "/SDA_CAM3") (class "Default")
      (node (ref "R48") (pin "2") (pinfunction "R2.1_2") (pintype "passive"))
      (node (ref "R51") (pin "3") (pinfunction "R3.1_3") (pintype "passive"))
      (node (ref "U26") (pin "7") (pinfunction "SD3_7") (pintype "passive"))
    )
    (net (code "80") (name "/VSYNC_CAM0") (class "Default")
      (node (ref "U31") (pin "5") (pinfunction "A_{1}_5") (pintype "passive"))
    )
    (net (code "81") (name "/VSYNC_CAM0_3V3") (class "Default")
      (node (ref "J7") (pin "32") (pinfunction "32_32") (pintype "passive"))
      (node (ref "U31") (pin "8") (pinfunction "B_{1}_8") (pintype "passive"))
    )
    (net (code "82") (name "/VSYNC_CAM1") (class "Default")
      (node (ref "U31") (pin "4") (pinfunction "A_{2}_4") (pintype "passive"))
    )
    (net (code "83") (name "/VSYNC_CAM1_3V3") (class "Default")
      (node (ref "J7") (pin "34") (pinfunction "34_34") (pintype "passive"))
      (node (ref "U31") (pin "1") (pinfunction "B_{2}_1") (pintype "passive"))
    )
    (net (code "84") (name "/VSYNC_CAM2") (class "Default")
      (node (ref "U32") (pin "5") (pinfunction "A_{1}_5") (pintype "passive"))
    )
    (net (code "85") (name "/VSYNC_CAM2_3V3") (class "Default")
      (node (ref "J8") (pin "32") (pinfunction "32_32") (pintype "passive"))
      (node (ref "U32") (pin "8") (pinfunction "B_{1}_8") (pintype "passive"))
    )
    (net (code "86") (name "/VSYNC_CAM3") (class "Default")
      (node (ref "U32") (pin "4") (pinfunction "A_{2}_4") (pintype "passive"))
    )
    (net (code "87") (name "/VSYNC_CAM3_3V3") (class "Default")
      (node (ref "J8") (pin "34") (pinfunction "34_34") (pintype "passive"))
      (node (ref "U32") (pin "1") (pinfunction "B_{2}_1") (pintype "passive"))
    )
    (net (code "88") (name "GND") (class "Default")
      (node (ref "C100") (pin "1") (pinfunction "1_1") (pintype "passive"))
      (node (ref "C101") (pin "1") (pinfunction "1_1") (pintype "passive"))
      (node (ref "C42") (pin "2") (pinfunction "2_2") (pintype "passive"))
      (node (ref "C43") (pin "2") (pinfunction "2_2") (pintype "passive"))
      (node (ref "C89") (pin "1") (pinfunction "1_1") (pintype "passive"))
      (node (ref "C90") (pin "2") (pinfunction "2_2") (pintype "passive"))
      (node (ref "C91") (pin "2") (pinfunction "2_2") (pintype "passive"))
      (node (ref "C94") (pin "1") (pinfunction "1_1") (pintype "passive"))
      (node (ref "C95") (pin "1") (pinfunction "1_1") (pintype "passive"))
      (node (ref "C96") (pin "1") (pinfunction "1_1") (pintype "passive"))
      (node (ref "C97") (pin "1") (pinfunction "1_1") (pintype "passive"))
      (node (ref "C98") (pin "1") (pinfunction "1_1") (pintype "passive"))
      (node (ref "C99") (pin "1") (pinfunction "1_1") (pintype "passive"))
      (node (ref "D18") (pin "1") (pinfunction "C_1") (pintype "passive"))
      (node (ref "D20") (pin "1") (pinfunction "C_1") (pintype "passive"))
      (node (ref "D24") (pin "1") (pinfunction "C_1") (pintype "passive"))
      (node (ref "D25") (pin "1") (pinfunction "C_1") (pintype "passive"))
      (node (ref "J7") (pin "12") (pinfunction "12_12") (pintype "passive"))
      (node (ref "J7") (pin "15") (pinfunction "15_15") (pintype "passive"))
      (node (ref "J7") (pin "18") (pinfunction "18_18") (pintype "passive"))
      (node (ref "J7") (pin "27") (pinfunction "27_27") (pintype "passive"))
      (node (ref "J7") (pin "30") (pinfunction "30_30") (pintype "passive"))
      (node (ref "J7") (pin "9") (pinfunction "9_9") (pintype "passive"))
      (node (ref "J7") (pin "MP1") (pinfunction "MP_MP1") (pintype "passive"))
      (node (ref "J7") (pin "MP2") (pinfunction "MP_MP2") (pintype "passive"))
      (node (ref "J8") (pin "12") (pinfunction "12_12") (pintype "passive"))
      (node (ref "J8") (pin "15") (pinfunction "15_15") (pintype "passive"))
      (node (ref "J8") (pin "18") (pinfunction "18_18") (pintype "passive"))
      (node (ref "J8") (pin "27") (pinfunction "27_27") (pintype "passive"))
      (node (ref "J8") (pin "30") (pinfunction "30_30") (pintype "passive"))
      (node (ref "J8") (pin "9") (pinfunction "9_9") (pintype "passive"))
      (node (ref "J8") (pin "MP1") (pinfunction "MP_MP1") (pintype "passive"))
      (node (ref "J8") (pin "MP2") (pinfunction "MP_MP2") (pintype "passive"))
      (node (ref "R10") (pin "1") (pinfunction "1_1") (pintype "passive"))
      (node (ref "R168") (pin "1") (pinfunction "1_1") (pintype "passive"))
      (node (ref "R180") (pin "1") (pinfunction "1_1") (pintype "passive"))
      (node (ref "R6") (pin "1") (pinfunction "1_1") (pintype "passive"))
      (node (ref "R7") (pin "1") (pinfunction "1_1") (pintype "passive"))
      (node (ref "R8") (pin "1") (pinfunction "1_1") (pintype "passive"))
      (node (ref "R9") (pin "1") (pinfunction "1_1") (pintype "passive"))
      (node (ref "U24") (pin "2") (pinfunction "GND_2") (pintype "passive"))
      (node (ref "U25") (pin "2") (pinfunction "GND_2") (pintype "passive"))
      (node (ref "U26") (pin "18") (pinfunction "A2_18") (pintype "passive"))
      (node (ref "U26") (pin "23") (pinfunction "A1_23") (pintype "passive"))
      (node (ref "U26") (pin "9") (pinfunction "GND_9") (pintype "passive"))
      (node (ref "U27") (pin "2") (pinfunction "GND_2") (pintype "passive"))
      (node (ref "U28") (pin "2") (pinfunction "GND_2") (pintype "passive"))
      (node (ref "U31") (pin "2") (pinfunction "GND_2") (pintype "passive"))
      (node (ref "U32") (pin "2") (pinfunction "GND_2") (pintype "passive"))
    )
    (net (code "89") (name "Net-(D18-A)") (class "Default")
      (node (ref "D18") (pin "2") (pinfunction "A_2") (pintype "passive"))
      (node (ref "R132") (pin "1") (pinfunction "1_1") (pintype "passive"))
    )
    (net (code "90") (name "Net-(D20-A)") (class "Default")
      (node (ref "D20") (pin "2") (pinfunction "A_2") (pintype "passive"))
      (node (ref "R197") (pin "1") (pinfunction "1_1") (pintype "passive"))
    )
    (net (code "91") (name "Net-(D24-A)") (class "Default")
      (node (ref "D24") (pin "2") (pinfunction "A_2") (pintype "passive"))
      (node (ref "R133") (pin "1") (pinfunction "1_1") (pintype "passive"))
    )
    (net (code "92") (name "Net-(D25-A)") (class "Default")
      (node (ref "D25") (pin "2") (pinfunction "A_2") (pintype "passive"))
      (node (ref "R206") (pin "1") (pinfunction "1_1") (pintype "passive"))
    )
    (net (code "93") (name "Net-(R50-R1.2)") (class "Default")
      (node (ref "J7") (pin "39") (pinfunction "39_39") (pintype "passive"))
      (node (ref "R50") (pin "8") (pinfunction "R1.2_8") (pintype "passive"))
    )
    (net (code "94") (name "Net-(R50-R2.2)") (class "Default")
      (node (ref "J7") (pin "40") (pinfunction "40_40") (pintype "passive"))
      (node (ref "R50") (pin "7") (pinfunction "R2.2_7") (pintype "passive"))
    )
    (net (code "95") (name "Net-(R50-R3.2)") (class "Default")
      (node (ref "J7") (pin "41") (pinfunction "41_41") (pintype "passive"))
      (node (ref "R50") (pin "6") (pinfunction "R3.2_6") (pintype "passive"))
    )
    (net (code "96") (name "Net-(R50-R4.2)") (class "Default")
      (node (ref "J7") (pin "42") (pinfunction "42_42") (pintype "passive"))
      (node (ref "R50") (pin "5") (pinfunction "R4.2_5") (pintype "passive"))
    )
    (net (code "97") (name "Net-(R51-R1.2)") (class "Default")
      (node (ref "J8") (pin "39") (pinfunction "39_39") (pintype "passive"))
      (node (ref "R51") (pin "8") (pinfunction "R1.2_8") (pintype "passive"))
    )
    (net (code "98") (name "Net-(R51-R2.2)") (class "Default")
      (node (ref "J8") (pin "40") (pinfunction "40_40") (pintype "passive"))
      (node (ref "R51") (pin "7") (pinfunction "R2.2_7") (pintype "passive"))
    )
    (net (code "99") (name "Net-(R51-R3.2)") (class "Default")
      (node (ref "J8") (pin "41") (pinfunction "41_41") (pintype "passive"))
      (node (ref "R51") (pin "6") (pinfunction "R3.2_6") (pintype "passive"))
    )
    (net (code "100") (name "Net-(R51-R4.2)") (class "Default")
      (node (ref "J8") (pin "42") (pinfunction "42_42") (pintype "passive"))
      (node (ref "R51") (pin "5") (pinfunction "R4.2_5") (pintype "passive"))
    )
    (net (code "101") (name "unconnected-(J7-Pad13)") (class "Default")
      (node (ref "J7") (pin "13") (pinfunction "13_13") (pintype "passive+no_connect"))
    )
    (net (code "102") (name "unconnected-(J7-Pad14)") (class "Default")
      (node (ref "J7") (pin "14") (pinfunction "14_14") (pintype "passive+no_connect"))
    )
    (net (code "103") (name "unconnected-(J7-Pad16)") (class "Default")
      (node (ref "J7") (pin "16") (pinfunction "16_16") (pintype "passive+no_connect"))
    )
    (net (code "104") (name "unconnected-(J7-Pad17)") (class "Default")
      (node (ref "J7") (pin "17") (pinfunction "17_17") (pintype "passive+no_connect"))
    )
    (net (code "105") (name "unconnected-(J7-Pad31)") (class "Default")
      (node (ref "J7") (pin "31") (pinfunction "31_31") (pintype "passive+no_connect"))
    )
    (net (code "106") (name "unconnected-(J7-Pad33)") (class "Default")
      (node (ref "J7") (pin "33") (pinfunction "33_33") (pintype "passive+no_connect"))
    )
    (net (code "107") (name "unconnected-(J7-Pad35)") (class "Default")
      (node (ref "J7") (pin "35") (pinfunction "35_35") (pintype "passive+no_connect"))
    )
    (net (code "108") (name "unconnected-(J7-Pad36)") (class "Default")
      (node (ref "J7") (pin "36") (pinfunction "36_36") (pintype "passive+no_connect"))
    )
    (net (code "109") (name "unconnected-(J7-Pad37)") (class "Default")
      (node (ref "J7") (pin "37") (pinfunction "37_37") (pintype "passive+no_connect"))
    )
    (net (code "110") (name "unconnected-(J7-Pad38)") (class "Default")
      (node (ref "J7") (pin "38") (pinfunction "38_38") (pintype "passive+no_connect"))
    )
    (net (code "111") (name "unconnected-(J7-Pad43)") (class "Default")
      (node (ref "J7") (pin "43") (pinfunction "43_43") (pintype "passive+no_connect"))
    )
    (net (code "112") (name "unconnected-(J7-Pad44)") (class "Default")
      (node (ref "J7") (pin "44") (pinfunction "44_44") (pintype "passive+no_connect"))
    )
    (net (code "113") (name "unconnected-(J7-Pad45)") (class "Default")
      (node (ref "J7") (pin "45") (pinfunction "45_45") (pintype "passive+no_connect"))
    )
    (net (code "114") (name "unconnected-(J7-Pad46)") (class "Default")
      (node (ref "J7") (pin "46") (pinfunction "46_46") (pintype "passive+no_connect"))
    )
    (net (code "115") (name "unconnected-(J8-Pad1)") (class "Default")
      (node (ref "J8") (pin "1") (pinfunction "1_1") (pintype "passive+no_connect"))
    )
    (net (code "116") (name "unconnected-(J8-Pad2)") (class "Default")
      (node (ref "J8") (pin "2") (pinfunction "2_2") (pintype "passive+no_connect"))
    )
    (net (code "117") (name "unconnected-(J8-Pad3)") (class "Default")
      (node (ref "J8") (pin "3") (pinfunction "3_3") (pintype "passive+no_connect"))
    )
    (net (code "118") (name "unconnected-(J8-Pad4)") (class "Default")
      (node (ref "J8") (pin "4") (pinfunction "4_4") (pintype "passive+no_connect"))
    )
    (net (code "119") (name "unconnected-(J8-Pad13)") (class "Default")
      (node (ref "J8") (pin "13") (pinfunction "13_13") (pintype "passive+no_connect"))
    )
    (net (code "120") (name "unconnected-(J8-Pad14)") (class "Default")
      (node (ref "J8") (pin "14") (pinfunction "14_14") (pintype "passive+no_connect"))
    )
    (net (code "121") (name "unconnected-(J8-Pad16)") (class "Default")
      (node (ref "J8") (pin "16") (pinfunction "16_16") (pintype "passive+no_connect"))
    )
    (net (code "122") (name "unconnected-(J8-Pad17)") (class "Default")
      (node (ref "J8") (pin "17") (pinfunction "17_17") (pintype "passive+no_connect"))
    )
    (net (code "123") (name "unconnected-(J8-Pad19)") (class "Default")
      (node (ref "J8") (pin "19") (pinfunction "19_19") (pintype "passive+no_connect"))
    )
    (net (code "124") (name "unconnected-(J8-Pad20)") (class "Default")
      (node (ref "J8") (pin "20") (pinfunction "20_20") (pintype "passive+no_connect"))
    )
    (net (code "125") (name "unconnected-(J8-Pad21)") (class "Default")
      (node (ref "J8") (pin "21") (pinfunction "21_21") (pintype "passive+no_connect"))
    )
    (net (code "126") (name "unconnected-(J8-Pad22)") (class "Default")
      (node (ref "J8") (pin "22") (pinfunction "22_22") (pintype "passive+no_connect"))
    )
    (net (code "127") (name "unconnected-(J8-Pad31)") (class "Default")
      (node (ref "J8") (pin "31") (pinfunction "31_31") (pintype "passive+no_connect"))
    )
    (net (code "128") (name "unconnected-(J8-Pad33)") (class "Default")
      (node (ref "J8") (pin "33") (pinfunction "33_33") (pintype "passive+no_connect"))
    )
    (net (code "129") (name "unconnected-(J8-Pad35)") (class "Default")
      (node (ref "J8") (pin "35") (pinfunction "35_35") (pintype "passive+no_connect"))
    )
    (net (code "130") (name "unconnected-(J8-Pad36)") (class "Default")
      (node (ref "J8") (pin "36") (pinfunction "36_36") (pintype "passive+no_connect"))
    )
    (net (code "131") (name "unconnected-(J8-Pad37)") (class "Default")
      (node (ref "J8") (pin "37") (pinfunction "37_37") (pintype "passive+no_connect"))
    )
    (net (code "132") (name "unconnected-(J8-Pad38)") (class "Default")
      (node (ref "J8") (pin "38") (pinfunction "38_38") (pintype "passive+no_connect"))
    )
    (net (code "133") (name "unconnected-(J8-Pad43)") (class "Default")
      (node (ref "J8") (pin "43") (pinfunction "43_43") (pintype "passive+no_connect"))
    )
    (net (code "134") (name "unconnected-(J8-Pad44)") (class "Default")
      (node (ref "J8") (pin "44") (pinfunction "44_44") (pintype "passive+no_connect"))
    )
    (net (code "135") (name "unconnected-(J8-Pad45)") (class "Default")
      (node (ref "J8") (pin "45") (pinfunction "45_45") (pintype "passive+no_connect"))
    )
    (net (code "136") (name "unconnected-(J8-Pad46)") (class "Default")
      (node (ref "J8") (pin "46") (pinfunction "46_46") (pintype "passive+no_connect"))
    )
    (net (code "137") (name "unconnected-(U26-EP-Pad25)") (class "Default")
      (node (ref "U26") (pin "25") (pinfunction "EP_25") (pintype "passive+no_connect"))
    )
  )
)
